# Dual.net
KiCad netlist of a schematic drawn in EAGLE
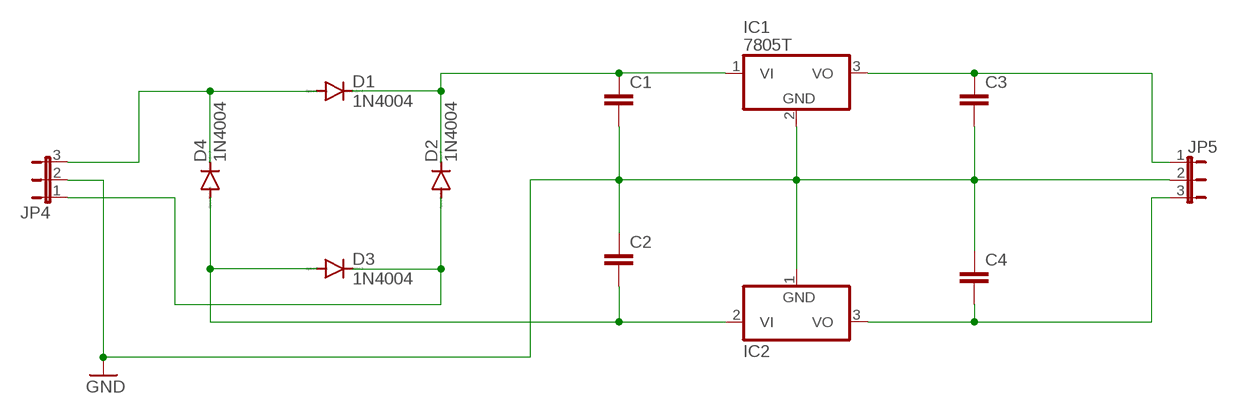
[diagram p0: schematic, sheet 1]

(export (version "E")
  (design (tool "Eeschema 10.0.6"))
  (components
    (comp (ref "C1")
      (value "C2,5-3")
      (footprint "eagle-import:C2.5-3")
      (libsource (lib "eagle-import") (part "C2,5-3"))
    )
    (comp (ref "C2")
      (value "C2,5-3")
      (footprint "eagle-import:C2.5-3")
      (libsource (lib "eagle-import") (part "C2,5-3"))
    )
    (comp (ref "C3")
      (value "C2,5-3")
      (footprint "eagle-import:C2.5-3")
      (libsource (lib "eagle-import") (part "C2,5-3"))
    )
    (comp (ref "C4")
      (value "C2,5-3")
      (footprint "eagle-import:C2.5-3")
      (libsource (lib "eagle-import") (part "C2,5-3"))
    )
    (comp (ref "D1")
      (value "1N4004")
      (footprint "eagle-import:DO41-10")
      (libsource (lib "eagle-import") (part "1N4004"))
    )
    (comp (ref "D2")
      (value "1N4004")
      (footprint "eagle-import:DO41-10")
      (libsource (lib "eagle-import") (part "1N4004"))
    )
    (comp (ref "D3")
      (value "1N4004")
      (footprint "eagle-import:DO41-10")
      (libsource (lib "eagle-import") (part "1N4004"))
    )
    (comp (ref "D4")
      (value "1N4004")
      (footprint "eagle-import:DO41-10")
      (libsource (lib "eagle-import") (part "1N4004"))
    )
    (comp (ref "IC1")
      (value "7805T")
      (footprint "eagle-import:TO220H")
      (libsource (lib "eagle-import") (part "78T05"))
    )
    (comp (ref "IC2")
      (value "7905T")
      (footprint "eagle-import:TO220H")
      (libsource (lib "eagle-import") (part "79T05"))
    )
    (comp (ref "JP4")
      (value "JP2W")
      (footprint "eagle-import:JP2W")
      (libsource (lib "eagle-import") (part "JP2W"))
    )
    (comp (ref "JP5")
      (value "JP2W")
      (footprint "eagle-import:JP2W")
      (libsource (lib "eagle-import") (part "JP2W"))
    )
  )
  (nets
    (net (code "1") (name "GND") (class "Default")
      (node (ref "C1") (pin "2") (pinfunction "2_2") (pintype "passive"))
      (node (ref "C2") (pin "1") (pinfunction "1_1") (pintype "passive"))
      (node (ref "C3") (pin "2") (pinfunction "2_2") (pintype "passive"))
      (node (ref "C4") (pin "1") (pinfunction "1_1") (pintype "passive"))
      (node (ref "IC1") (pin "2") (pinfunction "GND_2") (pintype "passive"))
      (node (ref "IC2") (pin "1") (pinfunction "GND_1") (pintype "passive"))
      (node (ref "JP4") (pin "2") (pinfunction "2_2") (pintype "passive"))
      (node (ref "JP5") (pin "2") (pinfunction "2_2") (pintype "passive"))
    )
    (net (code "2") (name "Net-(D1-PadA)") (class "Default")
      (node (ref "D1") (pin "A") (pinfunction "A_A") (pintype "passive"))
      (node (ref "D4") (pin "C") (pinfunction "C_C") (pintype "passive"))
      (node (ref "JP4") (pin "3") (pinfunction "3_3") (pintype "passive"))
    )
    (net (code "3") (name "Net-(D2-PadA)") (class "Default")
      (node (ref "D2") (pin "A") (pinfunction "A_A") (pintype "passive"))
      (node (ref "D3") (pin "C") (pinfunction "C_C") (pintype "passive"))
      (node (ref "JP4") (pin "1") (pinfunction "1_1") (pintype "passive"))
    )
    (net (code "4") (name "Net-(IC1-VI)") (class "Default")
      (node (ref "C1") (pin "1") (pinfunction "1_1") (pintype "passive"))
      (node (ref "D1") (pin "C") (pinfunction "C_C") (pintype "passive"))
      (node (ref "D2") (pin "C") (pinfunction "C_C") (pintype "passive"))
      (node (ref "IC1") (pin "1") (pinfunction "VI_1") (pintype "input"))
    )
    (net (code "5") (name "Net-(IC1-VO)") (class "Default")
      (node (ref "C3") (pin "1") (pinfunction "1_1") (pintype "passive"))
      (node (ref "IC1") (pin "3") (pinfunction "VO_3") (pintype "passive"))
      (node (ref "JP5") (pin "1") (pinfunction "1_1") (pintype "passive"))
    )
    (net (code "6") (name "Net-(IC2-VI)") (class "Default")
      (node (ref "C2") (pin "2") (pinfunction "2_2") (pintype "passive"))
      (node (ref "D3") (pin "A") (pinfunction "A_A") (pintype "passive"))
      (node (ref "D4") (pin "A") (pinfunction "A_A") (pintype "passive"))
      (node (ref "IC2") (pin "2") (pinfunction "VI_2") (pintype "input"))
    )
    (net (code "7") (name "Net-(IC2-VO)") (class "Default")
      (node (ref "C4") (pin "2") (pinfunction "2_2") (pintype "passive"))
      (node (ref "IC2") (pin "3") (pinfunction "VO_3") (pintype "passive"))
      (node (ref "JP5") (pin "3") (pinfunction "3_3") (pintype "passive"))
    )
  )
)
